# Power.net
KiCad netlist of a schematic drawn in Altium Designer
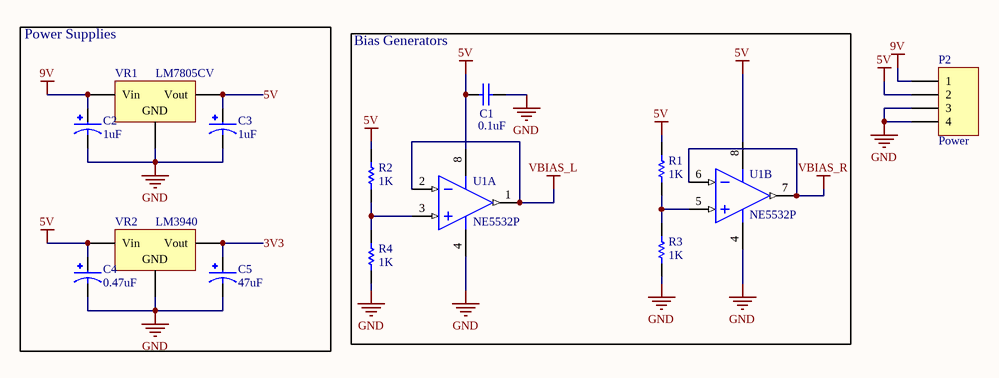
[diagram p0: Power.SchDoc]

(export (version "E")
  (design (tool "Eeschema 10.0.6"))
  (components
    (comp (ref "C1")
      (value "0.1uF")
      (footprint "RAD-0.1")
      (description "Capacitor")
      (fields (field (name "Comment") "Cap") (field (name "PUBLISHER") "Altium Limited"))
      (libsource (lib "Miscellaneous Devices") (part "Cap"))
    )
    (comp (ref "C2")
      (value "1uF")
      (footprint "CAPPRD200W50D500H1500")
      (description "1F 63V Aluminum Electrolytic Capacitors Radial, Can 5000 Hrs @ 105C")
      (fields (field (name "MP") "EEU-EB1J1R0") (field (name "MF") "Panasonic Electronic Components"))
      (libsource (lib "EEUEB1J1R0") (part "EEUEB1J1R0"))
    )
    (comp (ref "C3")
      (value "1uF")
      (footprint "CAPPRD200W50D500H1500")
      (description "1F 63V Aluminum Electrolytic Capacitors Radial, Can 5000 Hrs @ 105C")
      (fields (field (name "MP") "EEU-EB1J1R0") (field (name "MF") "Panasonic Electronic Components"))
      (libsource (lib "EEUEB1J1R0") (part "EEUEB1J1R0"))
    )
    (comp (ref "C4")
      (value "0.47uF")
      (footprint "CAPPRD200W50D500H1500")
      (description "1F 63V Aluminum Electrolytic Capacitors Radial, Can 5000 Hrs @ 105C")
      (fields (field (name "MP") "EEU-EB1J1R0") (field (name "MF") "Panasonic Electronic Components"))
      (libsource (lib "EEUEB1J1R0") (part "EEUEB1J1R0"))
    )
    (comp (ref "C5")
      (value "47uF")
      (footprint "CAPPRD200W50D500H1500")
      (description "1F 63V Aluminum Electrolytic Capacitors Radial, Can 5000 Hrs @ 105C")
      (fields (field (name "MP") "EEU-EB1J1R0") (field (name "MF") "Panasonic Electronic Components"))
      (libsource (lib "EEUEB1J1R0") (part "EEUEB1J1R0"))
    )
    (comp (ref "P2")
      (value "Power")
      (footprint "HDR1X4")
      (description "Header, 4-Pin")
      (fields (field (name "PUBLISHER") "Altium Limited"))
      (libsource (lib "Miscellaneous Connectors") (part "Header 4"))
    )
    (comp (ref "R1")
      (value "1K")
      (footprint "AXIAL-0.3")
      (description "Resistor")
      (fields (field (name "Comment") "Res1") (field (name "PUBLISHER") "Altium Limited"))
      (libsource (lib "Miscellaneous Devices") (part "Res1"))
    )
    (comp (ref "R2")
      (value "1K")
      (footprint "AXIAL-0.3")
      (description "Resistor")
      (fields (field (name "Comment") "Res1") (field (name "PUBLISHER") "Altium Limited"))
      (libsource (lib "Miscellaneous Devices") (part "Res1"))
    )
    (comp (ref "R3")
      (value "1K")
      (footprint "AXIAL-0.3")
      (description "Resistor")
      (fields (field (name "Comment") "Res1") (field (name "PUBLISHER") "Altium Limited"))
      (libsource (lib "Miscellaneous Devices") (part "Res1"))
    )
    (comp (ref "R4")
      (value "1K")
      (footprint "AXIAL-0.3")
      (description "Resistor")
      (fields (field (name "Comment") "Res1") (field (name "PUBLISHER") "Altium Limited"))
      (libsource (lib "Miscellaneous Devices") (part "Res1"))
    )
    (comp (ref "U1")
      (value "NE5532P")
      (footprint "TI-P8")
      (fields (field (name "MANUFACTURER") "Texas Instruments"))
      (libsource (lib "Texas_Instruments_NE5532P") (part "NE5532P"))
    )
    (comp (ref "VR1")
      (value "LM7805CV")
      (footprint "T03B")
      (description "Voltage Regulator")
      (fields (field (name "PUBLISHER") "Altium Limited"))
      (libsource (lib "Miscellaneous Devices") (part "Volt Reg"))
    )
    (comp (ref "VR2")
      (value "LM3940")
      (footprint "T03B")
      (description "Voltage Regulator")
      (fields (field (name "PUBLISHER") "Altium Limited"))
      (libsource (lib "Miscellaneous Devices") (part "Volt Reg"))
    )
  )
  (nets
    (net (code "1") (name "/3V3") (class "Default")
      (node (ref "C5") (pin "P") (pinfunction "P_P") (pintype "passive"))
      (node (ref "VR2") (pin "3") (pinfunction "Vout_3") (pintype "passive"))
    )
    (net (code "2") (name "5V") (class "Default")
      (node (ref "C1") (pin "1") (pinfunction "1_1") (pintype "passive"))
      (node (ref "C3") (pin "P") (pinfunction "P_P") (pintype "passive"))
      (node (ref "C4") (pin "P") (pinfunction "P_P") (pintype "passive"))
      (node (ref "P2") (pin "2") (pinfunction "2_2") (pintype "passive"))
      (node (ref "R1") (pin "2") (pinfunction "2_2") (pintype "passive"))
      (node (ref "R2") (pin "2") (pinfunction "2_2") (pintype "passive"))
      (node (ref "U1") (pin "8") (pinfunction "VCC+_8") (pintype "power_in"))
      (node (ref "VR1") (pin "3") (pinfunction "Vout_3") (pintype "passive"))
      (node (ref "VR2") (pin "1") (pinfunction "Vin_1") (pintype "passive"))
    )
    (net (code "3") (name "9V") (class "Default")
      (node (ref "C2") (pin "P") (pinfunction "P_P") (pintype "passive"))
      (node (ref "P2") (pin "1") (pinfunction "1_1") (pintype "passive"))
      (node (ref "VR1") (pin "1") (pinfunction "Vin_1") (pintype "passive"))
    )
    (net (code "4") (name "GND") (class "Default")
      (node (ref "C1") (pin "2") (pinfunction "2_2") (pintype "passive"))
      (node (ref "C2") (pin "N") (pinfunction "N_N") (pintype "passive"))
      (node (ref "C3") (pin "N") (pinfunction "N_N") (pintype "passive"))
      (node (ref "C4") (pin "N") (pinfunction "N_N") (pintype "passive"))
      (node (ref "C5") (pin "N") (pinfunction "N_N") (pintype "passive"))
      (node (ref "P2") (pin "3") (pinfunction "3_3") (pintype "passive"))
      (node (ref "P2") (pin "4") (pinfunction "4_4") (pintype "passive"))
      (node (ref "R3") (pin "1") (pinfunction "1_1") (pintype "passive"))
      (node (ref "R4") (pin "1") (pinfunction "1_1") (pintype "passive"))
      (node (ref "U1") (pin "4") (pinfunction "VCC-_4") (pintype "power_in"))
      (node (ref "VR1") (pin "2") (pinfunction "GND_2") (pintype "passive"))
      (node (ref "VR2") (pin "2") (pinfunction "GND_2") (pintype "passive"))
    )
    (net (code "5") (name "Net-(U1A-IN1+)") (class "Default")
      (node (ref "R2") (pin "1") (pinfunction "1_1") (pintype "passive"))
      (node (ref "R4") (pin "2") (pinfunction "2_2") (pintype "passive"))
      (node (ref "U1") (pin "3") (pinfunction "IN1+_3") (pintype "input"))
    )
    (net (code "6") (name "Net-(U1B-IN2+)") (class "Default")
      (node (ref "R1") (pin "1") (pinfunction "1_1") (pintype "passive"))
      (node (ref "R3") (pin "2") (pinfunction "2_2") (pintype "passive"))
      (node (ref "U1") (pin "5") (pinfunction "IN2+_5") (pintype "input"))
    )
    (net (code "7") (name "VBIAS_L") (class "Default")
      (node (ref "U1") (pin "1") (pinfunction "OUT1_1") (pintype "output"))
      (node (ref "U1") (pin "2") (pinfunction "IN1-_2") (pintype "input"))
    )
    (net (code "8") (name "VBIAS_R") (class "Default")
      (node (ref "U1") (pin "6") (pinfunction "IN2-_6") (pintype "input"))
      (node (ref "U1") (pin "7") (pinfunction "OUT2_7") (pintype "output"))
    )
  )
)
